# cpu2.net
KiCad netlist of a schematic drawn in EAGLE
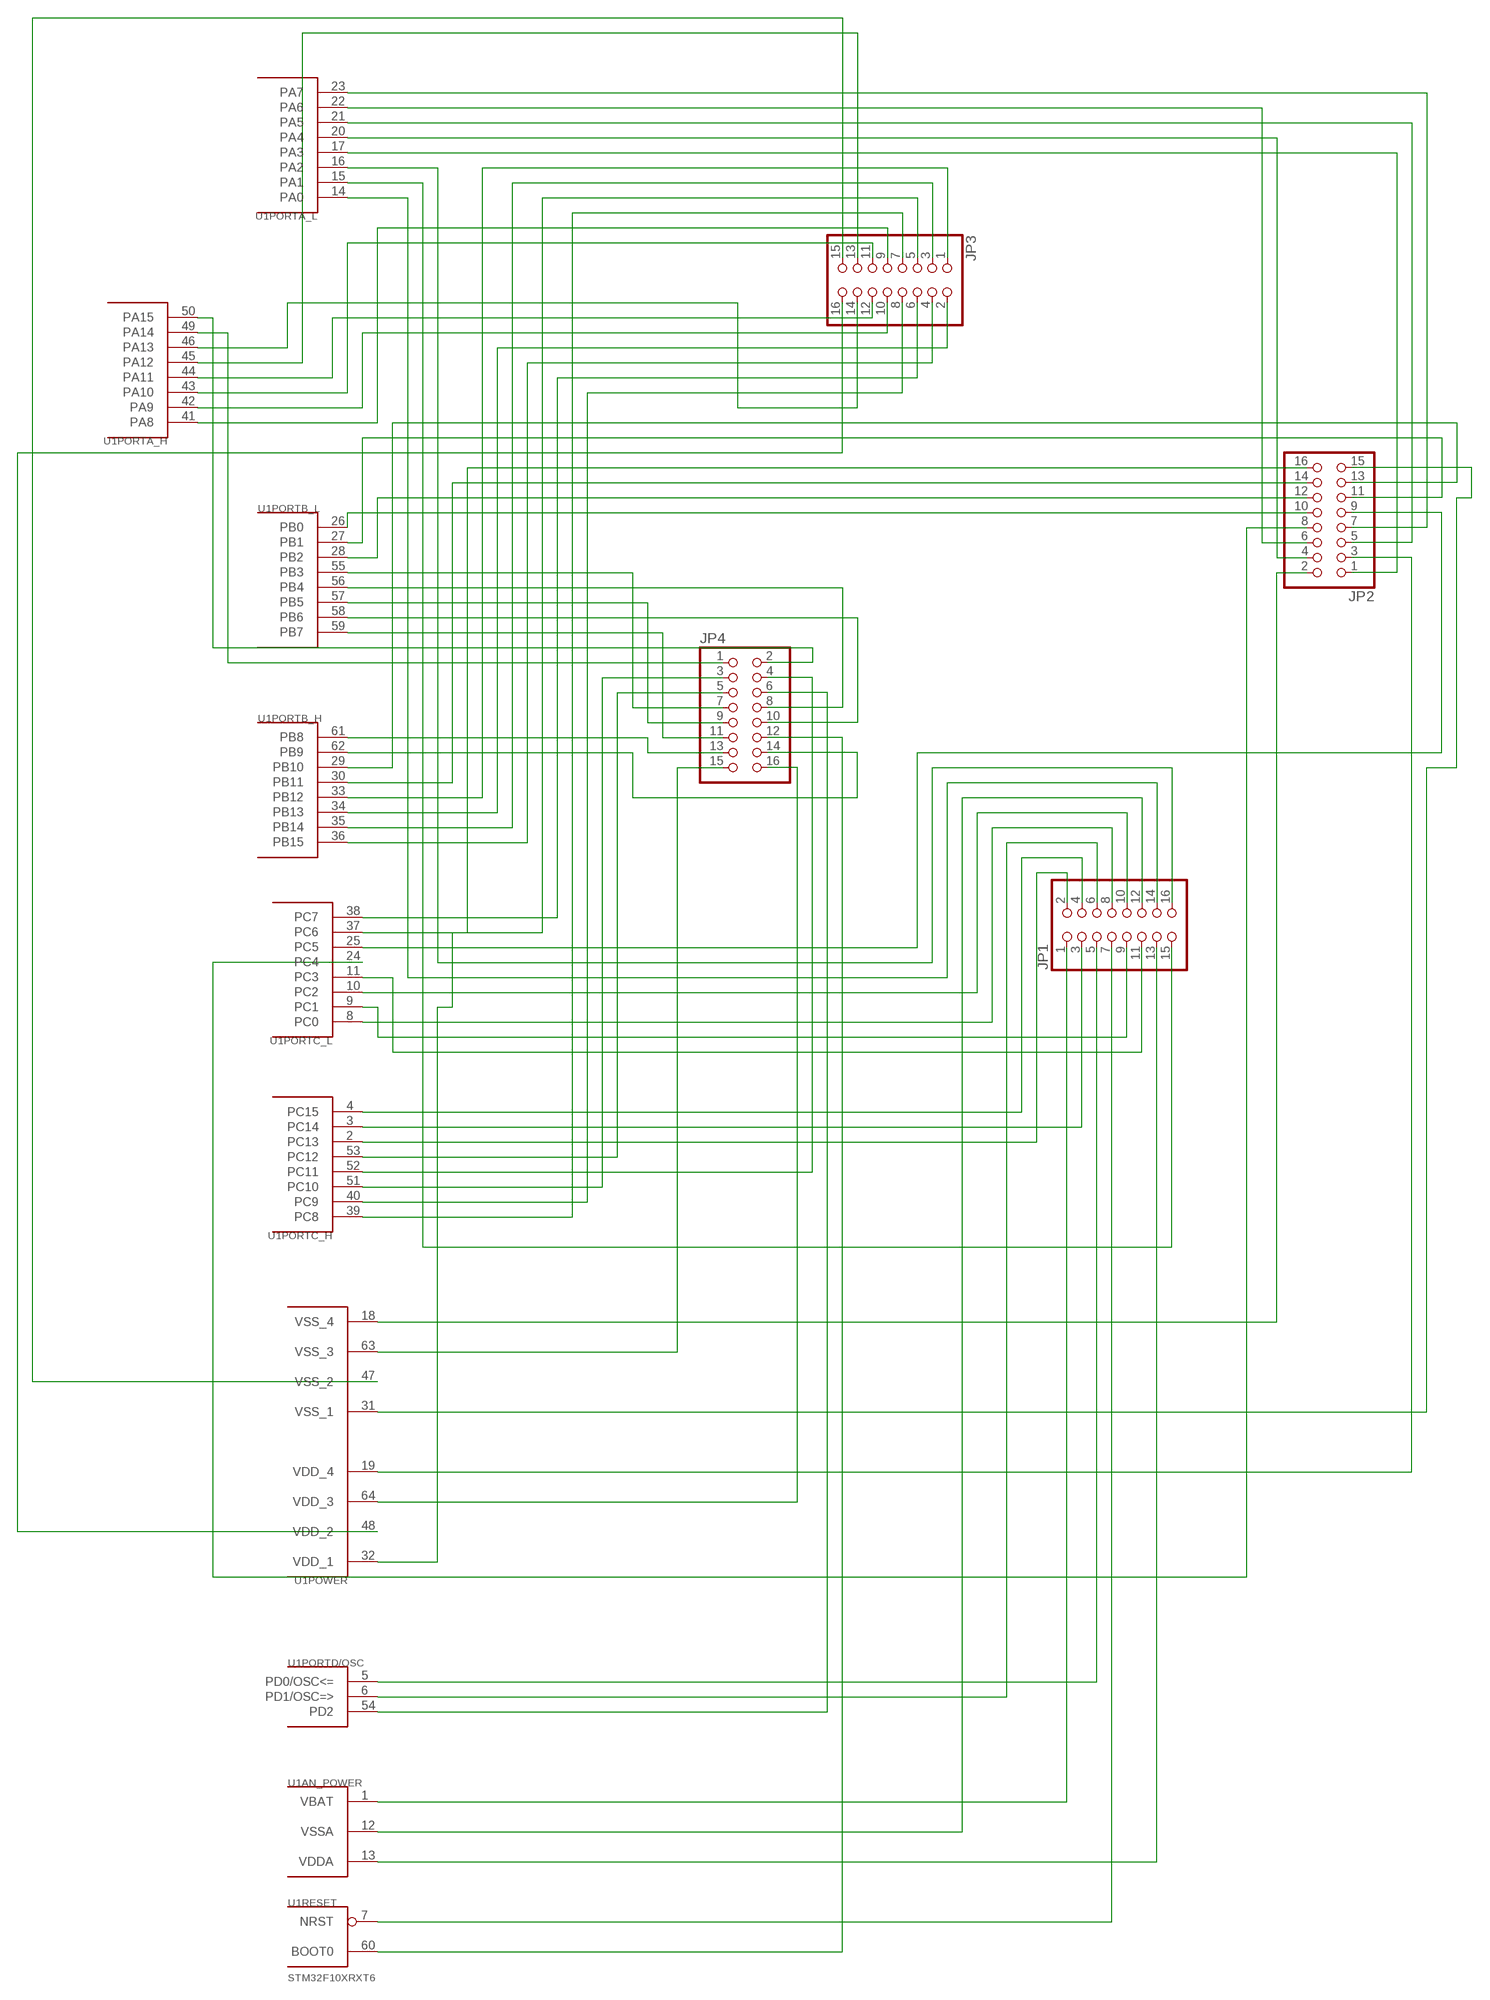
[diagram p0: schematic, sheet 1]

(export (version "E")
  (design (tool "Eeschema 10.0.6"))
  (components
    (comp (ref "JP1")
      (value "PINHD-2X8")
      (footprint "eagle-import:2X08")
      (libsource (lib "eagle-import") (part "PINHD-2X8"))
    )
    (comp (ref "JP2")
      (value "PINHD-2X8")
      (footprint "eagle-import:2X08")
      (libsource (lib "eagle-import") (part "PINHD-2X8"))
    )
    (comp (ref "JP3")
      (value "PINHD-2X8")
      (footprint "eagle-import:2X08")
      (libsource (lib "eagle-import") (part "PINHD-2X8"))
    )
    (comp (ref "JP4")
      (value "PINHD-2X8")
      (footprint "eagle-import:2X08")
      (libsource (lib "eagle-import") (part "PINHD-2X8"))
    )
    (comp (ref "U1")
      (value "STM32F10XRXT6")
      (footprint "eagle-import:TQFP64")
      (libsource (lib "eagle-import") (part "STM32F10XRXT6"))
    )
  )
  (nets
    (net (code "1") (name "Net-(U1A-VBAT)") (class "Default")
      (node (ref "JP1") (pin "1") (pinfunction "1_1") (pintype "passive"))
      (node (ref "U1") (pin "1") (pinfunction "VBAT_1") (pintype "power_in"))
    )
    (net (code "2") (name "Net-(U1A-VDDA)") (class "Default")
      (node (ref "JP1") (pin "13") (pinfunction "13_13") (pintype "passive"))
      (node (ref "U1") (pin "13") (pinfunction "VDDA_13") (pintype "power_in"))
    )
    (net (code "3") (name "Net-(U1A-VSSA)") (class "Default")
      (node (ref "JP1") (pin "12") (pinfunction "12_12") (pintype "passive"))
      (node (ref "U1") (pin "12") (pinfunction "VSSA_12") (pintype "power_in"))
    )
    (net (code "4") (name "Net-(U1B-PA8)") (class "Default")
      (node (ref "JP3") (pin "9") (pinfunction "9_9") (pintype "passive"))
      (node (ref "U1") (pin "41") (pinfunction "PA8_41") (pintype "bidirectional"))
    )
    (net (code "5") (name "Net-(U1B-PA9)") (class "Default")
      (node (ref "JP3") (pin "10") (pinfunction "10_10") (pintype "passive"))
      (node (ref "U1") (pin "42") (pinfunction "PA9_42") (pintype "bidirectional"))
    )
    (net (code "6") (name "Net-(U1B-PA10)") (class "Default")
      (node (ref "JP3") (pin "11") (pinfunction "11_11") (pintype "passive"))
      (node (ref "U1") (pin "43") (pinfunction "PA10_43") (pintype "bidirectional"))
    )
    (net (code "7") (name "Net-(U1B-PA11)") (class "Default")
      (node (ref "JP3") (pin "12") (pinfunction "12_12") (pintype "passive"))
      (node (ref "U1") (pin "44") (pinfunction "PA11_44") (pintype "bidirectional"))
    )
    (net (code "8") (name "Net-(U1B-PA12)") (class "Default")
      (node (ref "JP3") (pin "13") (pinfunction "13_13") (pintype "passive"))
      (node (ref "U1") (pin "45") (pinfunction "PA12_45") (pintype "bidirectional"))
    )
    (net (code "9") (name "Net-(U1B-PA13)") (class "Default")
      (node (ref "JP3") (pin "14") (pinfunction "14_14") (pintype "passive"))
      (node (ref "U1") (pin "46") (pinfunction "PA13_46") (pintype "bidirectional"))
    )
    (net (code "10") (name "Net-(U1B-PA14)") (class "Default")
      (node (ref "JP4") (pin "1") (pinfunction "1_1") (pintype "passive"))
      (node (ref "U1") (pin "49") (pinfunction "PA14_49") (pintype "bidirectional"))
    )
    (net (code "11") (name "Net-(U1B-PA15)") (class "Default")
      (node (ref "JP4") (pin "2") (pinfunction "2_2") (pintype "passive"))
      (node (ref "U1") (pin "50") (pinfunction "PA15_50") (pintype "bidirectional"))
    )
    (net (code "12") (name "Net-(U1C-PA0)") (class "Default")
      (node (ref "JP1") (pin "14") (pinfunction "14_14") (pintype "passive"))
      (node (ref "U1") (pin "14") (pinfunction "PA0_14") (pintype "bidirectional"))
    )
    (net (code "13") (name "Net-(U1C-PA1)") (class "Default")
      (node (ref "JP1") (pin "15") (pinfunction "15_15") (pintype "passive"))
      (node (ref "U1") (pin "15") (pinfunction "PA1_15") (pintype "bidirectional"))
    )
    (net (code "14") (name "Net-(U1C-PA2)") (class "Default")
      (node (ref "JP1") (pin "16") (pinfunction "16_16") (pintype "passive"))
      (node (ref "U1") (pin "16") (pinfunction "PA2_16") (pintype "bidirectional"))
    )
    (net (code "15") (name "Net-(U1C-PA3)") (class "Default")
      (node (ref "JP2") (pin "1") (pinfunction "1_1") (pintype "passive"))
      (node (ref "U1") (pin "17") (pinfunction "PA3_17") (pintype "bidirectional"))
    )
    (net (code "16") (name "Net-(U1C-PA4)") (class "Default")
      (node (ref "JP2") (pin "4") (pinfunction "4_4") (pintype "passive"))
      (node (ref "U1") (pin "20") (pinfunction "PA4_20") (pintype "bidirectional"))
    )
    (net (code "17") (name "Net-(U1C-PA5)") (class "Default")
      (node (ref "JP2") (pin "5") (pinfunction "5_5") (pintype "passive"))
      (node (ref "U1") (pin "21") (pinfunction "PA5_21") (pintype "bidirectional"))
    )
    (net (code "18") (name "Net-(U1C-PA6)") (class "Default")
      (node (ref "JP2") (pin "6") (pinfunction "6_6") (pintype "passive"))
      (node (ref "U1") (pin "22") (pinfunction "PA6_22") (pintype "bidirectional"))
    )
    (net (code "19") (name "Net-(U1C-PA7)") (class "Default")
      (node (ref "JP2") (pin "7") (pinfunction "7_7") (pintype "passive"))
      (node (ref "U1") (pin "23") (pinfunction "PA7_23") (pintype "bidirectional"))
    )
    (net (code "20") (name "Net-(U1D-PB8)") (class "Default")
      (node (ref "JP4") (pin "13") (pinfunction "13_13") (pintype "passive"))
      (node (ref "U1") (pin "61") (pinfunction "PB8_61") (pintype "bidirectional"))
    )
    (net (code "21") (name "Net-(U1D-PB9)") (class "Default")
      (node (ref "JP4") (pin "14") (pinfunction "14_14") (pintype "passive"))
      (node (ref "U1") (pin "62") (pinfunction "PB9_62") (pintype "bidirectional"))
    )
    (net (code "22") (name "Net-(U1D-PB10)") (class "Default")
      (node (ref "JP2") (pin "13") (pinfunction "13_13") (pintype "passive"))
      (node (ref "U1") (pin "29") (pinfunction "PB10_29") (pintype "bidirectional"))
    )
    (net (code "23") (name "Net-(U1D-PB11)") (class "Default")
      (node (ref "JP2") (pin "14") (pinfunction "14_14") (pintype "passive"))
      (node (ref "U1") (pin "30") (pinfunction "PB11_30") (pintype "bidirectional"))
    )
    (net (code "24") (name "Net-(U1D-PB12)") (class "Default")
      (node (ref "JP3") (pin "1") (pinfunction "1_1") (pintype "passive"))
      (node (ref "U1") (pin "33") (pinfunction "PB12_33") (pintype "bidirectional"))
    )
    (net (code "25") (name "Net-(U1D-PB13)") (class "Default")
      (node (ref "JP3") (pin "2") (pinfunction "2_2") (pintype "passive"))
      (node (ref "U1") (pin "34") (pinfunction "PB13_34") (pintype "bidirectional"))
    )
    (net (code "26") (name "Net-(U1D-PB14)") (class "Default")
      (node (ref "JP3") (pin "3") (pinfunction "3_3") (pintype "passive"))
      (node (ref "U1") (pin "35") (pinfunction "PB14_35") (pintype "bidirectional"))
    )
    (net (code "27") (name "Net-(U1D-PB15)") (class "Default")
      (node (ref "JP3") (pin "4") (pinfunction "4_4") (pintype "passive"))
      (node (ref "U1") (pin "36") (pinfunction "PB15_36") (pintype "bidirectional"))
    )
    (net (code "28") (name "Net-(U1E-PB0)") (class "Default")
      (node (ref "JP2") (pin "10") (pinfunction "10_10") (pintype "passive"))
      (node (ref "U1") (pin "26") (pinfunction "PB0_26") (pintype "bidirectional"))
    )
    (net (code "29") (name "Net-(U1E-PB1)") (class "Default")
      (node (ref "JP2") (pin "11") (pinfunction "11_11") (pintype "passive"))
      (node (ref "U1") (pin "27") (pinfunction "PB1_27") (pintype "bidirectional"))
    )
    (net (code "30") (name "Net-(U1E-PB2)") (class "Default")
      (node (ref "JP2") (pin "12") (pinfunction "12_12") (pintype "passive"))
      (node (ref "U1") (pin "28") (pinfunction "PB2_28") (pintype "bidirectional"))
    )
    (net (code "31") (name "Net-(U1E-PB3)") (class "Default")
      (node (ref "JP4") (pin "7") (pinfunction "7_7") (pintype "passive"))
      (node (ref "U1") (pin "55") (pinfunction "PB3_55") (pintype "bidirectional"))
    )
    (net (code "32") (name "Net-(U1E-PB4)") (class "Default")
      (node (ref "JP4") (pin "8") (pinfunction "8_8") (pintype "passive"))
      (node (ref "U1") (pin "56") (pinfunction "PB4_56") (pintype "bidirectional"))
    )
    (net (code "33") (name "Net-(U1E-PB5)") (class "Default")
      (node (ref "JP4") (pin "9") (pinfunction "9_9") (pintype "passive"))
      (node (ref "U1") (pin "57") (pinfunction "PB5_57") (pintype "bidirectional"))
    )
    (net (code "34") (name "Net-(U1E-PB6)") (class "Default")
      (node (ref "JP4") (pin "10") (pinfunction "10_10") (pintype "passive"))
      (node (ref "U1") (pin "58") (pinfunction "PB6_58") (pintype "bidirectional"))
    )
    (net (code "35") (name "Net-(U1E-PB7)") (class "Default")
      (node (ref "JP4") (pin "11") (pinfunction "11_11") (pintype "passive"))
      (node (ref "U1") (pin "59") (pinfunction "PB7_59") (pintype "bidirectional"))
    )
    (net (code "36") (name "Net-(U1F-PC8)") (class "Default")
      (node (ref "JP3") (pin "7") (pinfunction "7_7") (pintype "passive"))
      (node (ref "U1") (pin "39") (pinfunction "PC8_39") (pintype "bidirectional"))
    )
    (net (code "37") (name "Net-(U1F-PC9)") (class "Default")
      (node (ref "JP3") (pin "8") (pinfunction "8_8") (pintype "passive"))
      (node (ref "U1") (pin "40") (pinfunction "PC9_40") (pintype "bidirectional"))
    )
    (net (code "38") (name "Net-(U1F-PC10)") (class "Default")
      (node (ref "JP4") (pin "3") (pinfunction "3_3") (pintype "passive"))
      (node (ref "U1") (pin "51") (pinfunction "PC10_51") (pintype "bidirectional"))
    )
    (net (code "39") (name "Net-(U1F-PC11)") (class "Default")
      (node (ref "JP4") (pin "4") (pinfunction "4_4") (pintype "passive"))
      (node (ref "U1") (pin "52") (pinfunction "PC11_52") (pintype "bidirectional"))
    )
    (net (code "40") (name "Net-(U1F-PC12)") (class "Default")
      (node (ref "JP4") (pin "5") (pinfunction "5_5") (pintype "passive"))
      (node (ref "U1") (pin "53") (pinfunction "PC12_53") (pintype "bidirectional"))
    )
    (net (code "41") (name "Net-(U1F-PC13)") (class "Default")
      (node (ref "JP1") (pin "2") (pinfunction "2_2") (pintype "passive"))
      (node (ref "U1") (pin "2") (pinfunction "PC13_2") (pintype "bidirectional"))
    )
    (net (code "42") (name "Net-(U1F-PC14)") (class "Default")
      (node (ref "JP1") (pin "3") (pinfunction "3_3") (pintype "passive"))
      (node (ref "U1") (pin "3") (pinfunction "PC14_3") (pintype "bidirectional"))
    )
    (net (code "43") (name "Net-(U1F-PC15)") (class "Default")
      (node (ref "JP1") (pin "4") (pinfunction "4_4") (pintype "passive"))
      (node (ref "U1") (pin "4") (pinfunction "PC15_4") (pintype "bidirectional"))
    )
    (net (code "44") (name "Net-(U1G-PC0)") (class "Default")
      (node (ref "JP1") (pin "8") (pinfunction "8_8") (pintype "passive"))
      (node (ref "U1") (pin "8") (pinfunction "PC0_8") (pintype "bidirectional"))
    )
    (net (code "45") (name "Net-(U1G-PC1)") (class "Default")
      (node (ref "JP1") (pin "9") (pinfunction "9_9") (pintype "passive"))
      (node (ref "U1") (pin "9") (pinfunction "PC1_9") (pintype "bidirectional"))
    )
    (net (code "46") (name "Net-(U1G-PC2)") (class "Default")
      (node (ref "JP1") (pin "10") (pinfunction "10_10") (pintype "passive"))
      (node (ref "U1") (pin "10") (pinfunction "PC2_10") (pintype "bidirectional"))
    )
    (net (code "47") (name "Net-(U1G-PC3)") (class "Default")
      (node (ref "JP1") (pin "11") (pinfunction "11_11") (pintype "passive"))
      (node (ref "U1") (pin "11") (pinfunction "PC3_11") (pintype "bidirectional"))
    )
    (net (code "48") (name "Net-(U1G-PC4)") (class "Default")
      (node (ref "JP2") (pin "8") (pinfunction "8_8") (pintype "passive"))
      (node (ref "U1") (pin "24") (pinfunction "PC4_24") (pintype "bidirectional"))
    )
    (net (code "49") (name "Net-(U1G-PC5)") (class "Default")
      (node (ref "JP2") (pin "9") (pinfunction "9_9") (pintype "passive"))
      (node (ref "U1") (pin "25") (pinfunction "PC5_25") (pintype "bidirectional"))
    )
    (net (code "50") (name "Net-(U1G-PC6)") (class "Default")
      (node (ref "JP3") (pin "5") (pinfunction "5_5") (pintype "passive"))
      (node (ref "U1") (pin "37") (pinfunction "PC6_37") (pintype "bidirectional"))
    )
    (net (code "51") (name "Net-(U1G-PC7)") (class "Default")
      (node (ref "JP3") (pin "6") (pinfunction "6_6") (pintype "passive"))
      (node (ref "U1") (pin "38") (pinfunction "PC7_38") (pintype "bidirectional"))
    )
    (net (code "52") (name "Net-(U1H-PD0{slash}OSC<=)") (class "Default")
      (node (ref "JP1") (pin "5") (pinfunction "5_5") (pintype "passive"))
      (node (ref "U1") (pin "5") (pinfunction "PD0/OSC<=_5") (pintype "bidirectional"))
    )
    (net (code "53") (name "Net-(U1H-PD1{slash}OSC=>)") (class "Default")
      (node (ref "JP1") (pin "6") (pinfunction "6_6") (pintype "passive"))
      (node (ref "U1") (pin "6") (pinfunction "PD1/OSC=>_6") (pintype "bidirectional"))
    )
    (net (code "54") (name "Net-(U1H-PD2)") (class "Default")
      (node (ref "JP4") (pin "6") (pinfunction "6_6") (pintype "passive"))
      (node (ref "U1") (pin "54") (pinfunction "PD2_54") (pintype "bidirectional"))
    )
    (net (code "55") (name "Net-(U1I-VDD_1)") (class "Default")
      (node (ref "JP2") (pin "16") (pinfunction "16_16") (pintype "passive"))
      (node (ref "U1") (pin "32") (pinfunction "VDD_1_32") (pintype "power_in"))
    )
    (net (code "56") (name "Net-(U1I-VDD_2)") (class "Default")
      (node (ref "JP3") (pin "16") (pinfunction "16_16") (pintype "passive"))
      (node (ref "U1") (pin "48") (pinfunction "VDD_2_48") (pintype "power_in"))
    )
    (net (code "57") (name "Net-(U1I-VDD_3)") (class "Default")
      (node (ref "JP4") (pin "16") (pinfunction "16_16") (pintype "passive"))
      (node (ref "U1") (pin "64") (pinfunction "VDD_3_64") (pintype "power_in"))
    )
    (net (code "58") (name "Net-(U1I-VDD_4)") (class "Default")
      (node (ref "JP2") (pin "3") (pinfunction "3_3") (pintype "passive"))
      (node (ref "U1") (pin "19") (pinfunction "VDD_4_19") (pintype "power_in"))
    )
    (net (code "59") (name "Net-(U1I-VSS_1)") (class "Default")
      (node (ref "JP2") (pin "15") (pinfunction "15_15") (pintype "passive"))
      (node (ref "U1") (pin "31") (pinfunction "VSS_1_31") (pintype "power_in"))
    )
    (net (code "60") (name "Net-(U1I-VSS_2)") (class "Default")
      (node (ref "JP3") (pin "15") (pinfunction "15_15") (pintype "passive"))
      (node (ref "U1") (pin "47") (pinfunction "VSS_2_47") (pintype "power_in"))
    )
    (net (code "61") (name "Net-(U1I-VSS_3)") (class "Default")
      (node (ref "JP4") (pin "15") (pinfunction "15_15") (pintype "passive"))
      (node (ref "U1") (pin "63") (pinfunction "VSS_3_63") (pintype "power_in"))
    )
    (net (code "62") (name "Net-(U1I-VSS_4)") (class "Default")
      (node (ref "JP2") (pin "2") (pinfunction "2_2") (pintype "passive"))
      (node (ref "U1") (pin "18") (pinfunction "VSS_4_18") (pintype "power_in"))
    )
    (net (code "63") (name "Net-(U1J-BOOT0)") (class "Default")
      (node (ref "JP4") (pin "12") (pinfunction "12_12") (pintype "passive"))
      (node (ref "U1") (pin "60") (pinfunction "BOOT0_60") (pintype "input"))
    )
    (net (code "64") (name "Net-(U1J-NRST)") (class "Default")
      (node (ref "JP1") (pin "7") (pinfunction "7_7") (pintype "passive"))
      (node (ref "U1") (pin "7") (pinfunction "NRST_7") (pintype "input"))
    )
  )
)
